# Prj_CamBienLua.net
KiCad netlist of a schematic drawn in Altium Designer
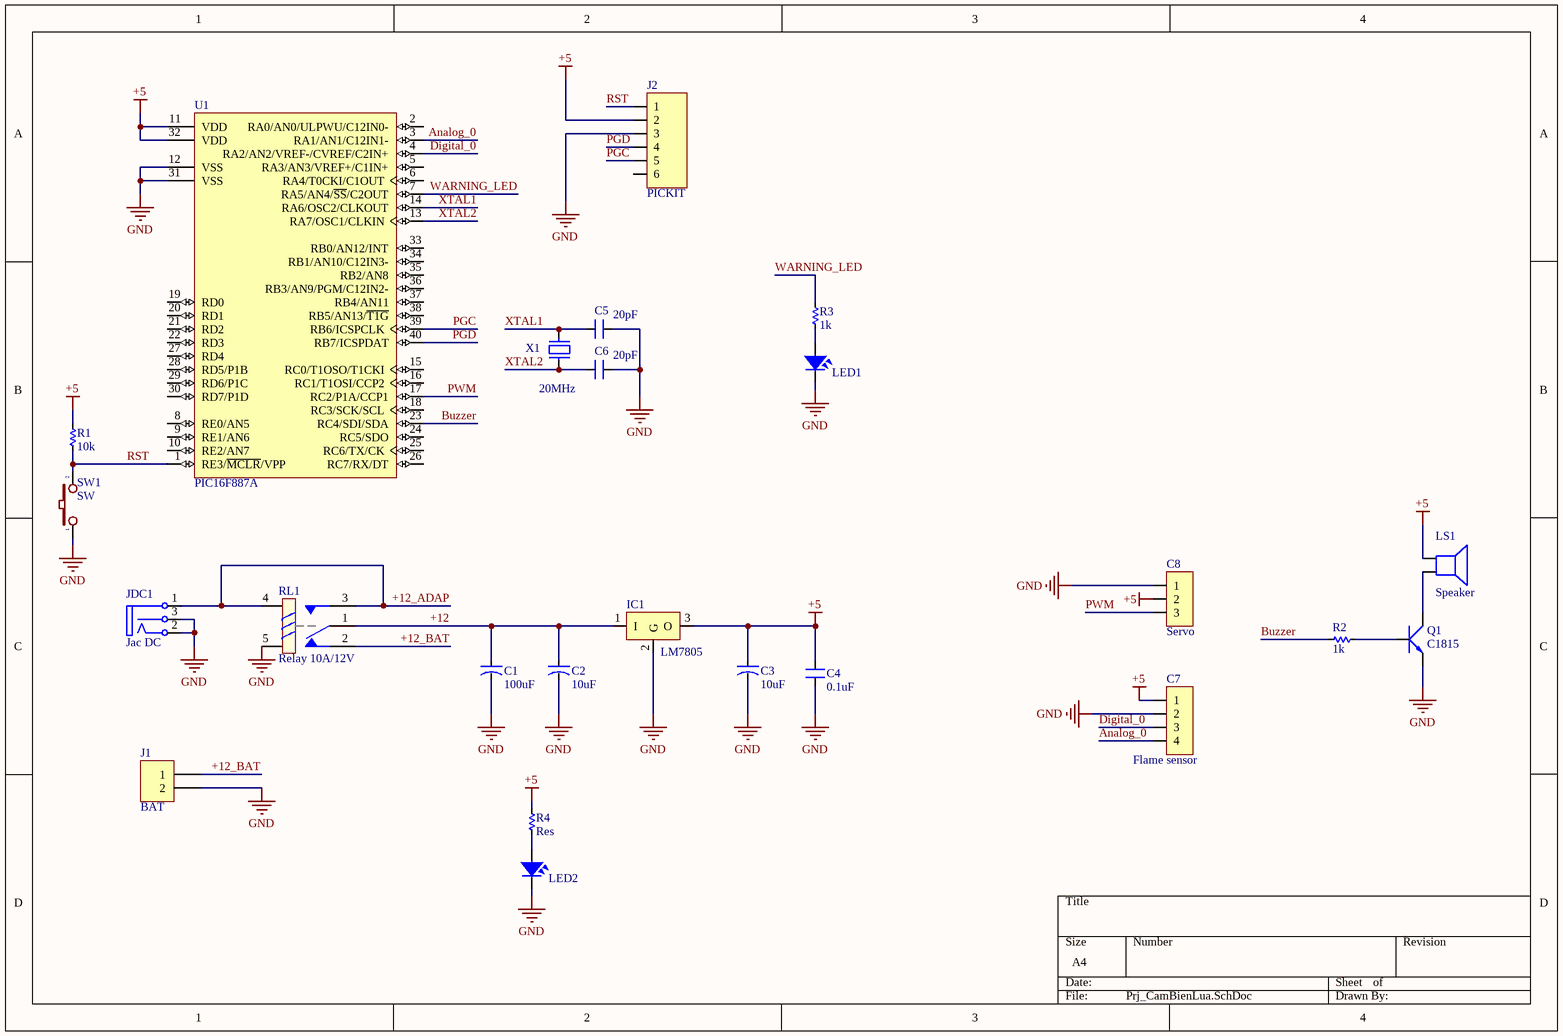
[diagram p0: Prj_CamBienLua.SchDoc]

(export (version "E")
  (design (tool "Eeschema 10.0.6"))
  (components
    (comp (ref "C1")
      (value "100uF")
      (footprint "CA-ALU-5")
      (description "Capacitor (Semiconductor SIM Model)")
      (fields (field (name "PUBLISHER") "Altium Limited"))
      (libsource (lib "Library") (part "CN-ALU-DIP"))
    )
    (comp (ref "C2")
      (value "10uF")
      (footprint "CA-ALU-5")
      (description "Capacitor (Semiconductor SIM Model)")
      (fields (field (name "PUBLISHER") "Altium Limited"))
      (libsource (lib "Library") (part "CN-ALU-DIP"))
    )
    (comp (ref "C3")
      (value "10uF")
      (footprint "CA-ALU-5")
      (description "Capacitor (Semiconductor SIM Model)")
      (fields (field (name "PUBLISHER") "Altium Limited"))
      (libsource (lib "Library") (part "CN-ALU-DIP"))
    )
    (comp (ref "C4") (value "0.1uF") (footprint "CN1.5") (libsource (lib "Library") (part "CN")))
    (comp (ref "C5") (value "20pF") (footprint "CN1.5") (libsource (lib "Library") (part "CN")))
    (comp (ref "C6") (value "20pF") (footprint "CN1.5") (libsource (lib "Library") (part "CN")))
    (comp (ref "C7")
      (value "Flame sensor")
      (footprint "JP4-C1T")
      (description "WR-PHD 2.54 mm Angled Socket Header")
      (fields
        (field (name "MANUFACTURER") "Würth Elektronik eiSos GmbH")
        (field (name "PARTNO") "613004143121")
        (field (name "CREATED BY") "Karrer Zheng")
      )
      (libsource (lib "Library") (part "JP4"))
    )
    (comp (ref "C8")
      (value "Servo")
      (footprint "JP3-D1T")
      (description "WR-PHD 2.54 mm Angled Socket Header")
      (fields
        (field (name "MANUFACTURER") "Würth Elektronik eiSos GmbH")
        (field (name "PARTNO") "613003143121")
        (field (name "CREATED BY") "Karrer Zheng")
      )
      (libsource (lib "Library") (part "JP3"))
    )
    (comp (ref "IC1")
      (value "LM7805")
      (footprint "TO220-123")
      (description "Positive Voltage Regulator")
      (fields (field (name "PUBLISHER") "Altium Limited"))
      (libsource (lib "Library") (part "LM78xx"))
    )
    (comp (ref "J1")
      (value "BAT")
      (footprint "KF2-5.08")
      (fields
        (field (name "MANUFACTURER") "Würth Elektronik eiSos GmbH")
        (field (name "PARTNO") "691103110002")
        (field (name "CREATED BY") "Karrer Zheng")
      )
      (libsource (lib "Library") (part "KF2"))
    )
    (comp (ref "J2")
      (value "PICKIT")
      (footprint "JP6-C1T")
      (description "WR-PHD 2.54 mm Angled Socket Header")
      (fields
        (field (name "MANUFACTURER") "Würth Elektronik eiSos GmbH")
        (field (name "PARTNO") "613006143121")
        (field (name "CREATED BY") "Karrer Zheng")
      )
      (libsource (lib "Library") (part "JP6"))
    )
    (comp (ref "JDC1")
      (value "Jac DC")
      (footprint "DC0")
      (description "Jac DC input")
      (libsource (lib "Library") (part "DCIN"))
    )
    (comp (ref "LED1")
      (value "LED")
      (footprint "LED-3MM-RED")
      (description "LED Single colour Green and Red")
      (libsource (lib "Library") (part "LED"))
    )
    (comp (ref "LED2")
      (value "LED")
      (footprint "LED-3MM-RED")
      (description "LED Single colour Green and Red")
      (libsource (lib "Library") (part "LED"))
    )
    (comp (ref "LS1")
      (value "Speaker")
      (footprint "SPEAKER")
      (description "Loudspeaker")
      (fields (field (name "PUBLISHER") "Altium Limited"))
      (libsource (lib "Library") (part "Speaker"))
    )
    (comp (ref "Q1")
      (value "C1815")
      (footprint "TO92-123")
      (description "NPN 600mW, ECB")
      (libsource (lib "Library") (part "C458"))
    )
    (comp (ref "R1")
      (value "10k")
      (footprint "RES-1/4W")
      (description "Res")
      (fields
        (field (name "MANUFACTURER") "Generic Components")
        (field (name "PUBLISHER") "Altium Hobart Technology Centre")
      )
      (libsource (lib "Library") (part "Res"))
    )
    (comp (ref "R2")
      (value "1k")
      (footprint "RES-1/4W")
      (description "Res")
      (fields
        (field (name "MANUFACTURER") "Generic Components")
        (field (name "PUBLISHER") "Altium Hobart Technology Centre")
      )
      (libsource (lib "Library") (part "Res"))
    )
    (comp (ref "R3")
      (value "1k")
      (footprint "RES-1/4W")
      (description "Res")
      (fields
        (field (name "MANUFACTURER") "Generic Components")
        (field (name "PUBLISHER") "Altium Hobart Technology Centre")
      )
      (libsource (lib "Library") (part "Res"))
    )
    (comp (ref "R4")
      (value "Res")
      (footprint "RES-1/4W")
      (fields
        (field (name "MANUFACTURER") "Generic Components")
        (field (name "PUBLISHER") "Altium Hobart Technology Centre")
      )
      (libsource (lib "Library") (part "Res"))
    )
    (comp (ref "RL1")
      (value "Relay 10A/12V")
      (footprint "Relay - SRD-03VDC-SL-C")
      (description "Relay SPDT,10A - 12VDC 5 Pin")
      (libsource (lib "Library") (part "Relay 5"))
    )
    (comp (ref "SW1")
      (value "SW")
      (footprint "SW2-DIP")
      (description "Switch button 2 pin")
      (libsource (lib "Library") (part "SW2"))
    )
    (comp (ref "U1")
      (value "PIC16F887A")
      (footprint "DIP40/W0.6")
      (fields (field (name "PUBLISHER") "Altium Limited"))
      (libsource (lib "Library") (part "PIC16F887-PU"))
    )
    (comp (ref "X1")
      (value "20MHz")
      (footprint "XT2")
      (description "Crystal, 32.768 KHz, -40 to 85 degC, 3.2 x 1.5 x 0.9 mm SMD")
      (libsource (lib "Library") (part "XT2"))
    )
  )
  (nets
    (net (code "1") (name "+5") (class "Default")
      (node (ref "C3") (pin "1") (pinfunction "1_1") (pintype "passive"))
      (node (ref "C4") (pin "2") (pinfunction "2_2") (pintype "passive"))
      (node (ref "C7") (pin "1") (pinfunction "1_1") (pintype "passive"))
      (node (ref "C8") (pin "2") (pinfunction "2_2") (pintype "passive"))
      (node (ref "IC1") (pin "3") (pinfunction "O_3") (pintype "power_in"))
      (node (ref "J2") (pin "2") (pinfunction "2_2") (pintype "passive"))
      (node (ref "LS1") (pin "1") (pinfunction "1_1") (pintype "passive"))
      (node (ref "R1") (pin "2") (pinfunction "2_2") (pintype "passive"))
      (node (ref "R4") (pin "1") (pinfunction "1_1") (pintype "passive"))
      (node (ref "U1") (pin "11") (pinfunction "VDD_11") (pintype "power_in"))
      (node (ref "U1") (pin "32") (pinfunction "VDD_32") (pintype "power_in"))
    )
    (net (code "2") (name "/+12") (class "Default")
      (node (ref "C1") (pin "1") (pinfunction "1_1") (pintype "passive"))
      (node (ref "C2") (pin "1") (pinfunction "1_1") (pintype "passive"))
      (node (ref "IC1") (pin "1") (pinfunction "I_1") (pintype "power_in"))
      (node (ref "RL1") (pin "1") (pinfunction "1_1") (pintype "passive"))
    )
    (net (code "3") (name "/+12_ADAP") (class "Default")
      (node (ref "JDC1") (pin "1") (pinfunction "T_1") (pintype "passive"))
      (node (ref "RL1") (pin "3") (pinfunction "3_3") (pintype "passive"))
      (node (ref "RL1") (pin "4") (pinfunction "4_4") (pintype "passive"))
    )
    (net (code "4") (name "/+12_BAT") (class "Default")
      (node (ref "J1") (pin "1") (pinfunction "1_1") (pintype "passive"))
      (node (ref "RL1") (pin "2") (pinfunction "2_2") (pintype "passive"))
    )
    (net (code "5") (name "/Analog_0") (class "Default")
      (node (ref "C7") (pin "4") (pinfunction "4_4") (pintype "passive"))
      (node (ref "U1") (pin "3") (pinfunction "RA1/AN1/C12IN1-_3") (pintype "bidirectional"))
    )
    (net (code "6") (name "/Buzzer") (class "Default")
      (node (ref "R2") (pin "1") (pinfunction "1_1") (pintype "passive"))
      (node (ref "U1") (pin "23") (pinfunction "RC4/SDI/SDA_23") (pintype "bidirectional"))
    )
    (net (code "7") (name "/Digital_0") (class "Default")
      (node (ref "C7") (pin "3") (pinfunction "3_3") (pintype "passive"))
      (node (ref "U1") (pin "4") (pinfunction "RA2/AN2/VREF-/CVREF/C2IN+_4") (pintype "bidirectional"))
    )
    (net (code "8") (name "/PGC") (class "Default")
      (node (ref "J2") (pin "5") (pinfunction "5_5") (pintype "passive"))
      (node (ref "U1") (pin "39") (pinfunction "RB6/ICSPCLK_39") (pintype "bidirectional"))
    )
    (net (code "9") (name "/PGD") (class "Default")
      (node (ref "J2") (pin "4") (pinfunction "4_4") (pintype "passive"))
      (node (ref "U1") (pin "40") (pinfunction "RB7/ICSPDAT_40") (pintype "bidirectional"))
    )
    (net (code "10") (name "/PWM") (class "Default")
      (node (ref "C8") (pin "3") (pinfunction "3_3") (pintype "passive"))
      (node (ref "U1") (pin "17") (pinfunction "RC2/P1A/CCP1_17") (pintype "bidirectional"))
    )
    (net (code "11") (name "/RST") (class "Default")
      (node (ref "J2") (pin "1") (pinfunction "1_1") (pintype "passive"))
      (node (ref "R1") (pin "1") (pinfunction "1_1") (pintype "passive"))
      (node (ref "SW1") (pin "2") (pinfunction "2_2") (pintype "passive"))
      (node (ref "U1") (pin "1") (pinfunction "RE3/~{MCLR}/VPP_1") (pintype "bidirectional"))
    )
    (net (code "12") (name "/WARNING_LED") (class "Default")
      (node (ref "R3") (pin "1") (pinfunction "1_1") (pintype "passive"))
      (node (ref "U1") (pin "7") (pinfunction "RA5/AN4/~{SS}/C2OUT_7") (pintype "bidirectional"))
    )
    (net (code "13") (name "/XTAL1") (class "Default")
      (node (ref "C5") (pin "1") (pinfunction "1_1") (pintype "passive"))
      (node (ref "U1") (pin "14") (pinfunction "RA6/OSC2/CLKOUT_14") (pintype "bidirectional"))
      (node (ref "X1") (pin "2") (pinfunction "2_2") (pintype "passive"))
    )
    (net (code "14") (name "/XTAL2") (class "Default")
      (node (ref "C6") (pin "1") (pinfunction "1_1") (pintype "passive"))
      (node (ref "U1") (pin "13") (pinfunction "RA7/OSC1/CLKIN_13") (pintype "bidirectional"))
      (node (ref "X1") (pin "1") (pinfunction "1_1") (pintype "passive"))
    )
    (net (code "15") (name "GND") (class "Default")
      (node (ref "C1") (pin "2") (pinfunction "2_2") (pintype "passive"))
      (node (ref "C2") (pin "2") (pinfunction "2_2") (pintype "passive"))
      (node (ref "C3") (pin "2") (pinfunction "2_2") (pintype "passive"))
      (node (ref "C4") (pin "1") (pinfunction "1_1") (pintype "passive"))
      (node (ref "C5") (pin "2") (pinfunction "2_2") (pintype "passive"))
      (node (ref "C6") (pin "2") (pinfunction "2_2") (pintype "passive"))
      (node (ref "C7") (pin "2") (pinfunction "2_2") (pintype "passive"))
      (node (ref "C8") (pin "1") (pinfunction "1_1") (pintype "passive"))
      (node (ref "IC1") (pin "2") (pinfunction "G_2") (pintype "power_in"))
      (node (ref "J1") (pin "2") (pinfunction "2_2") (pintype "passive"))
      (node (ref "J2") (pin "3") (pinfunction "3_3") (pintype "passive"))
      (node (ref "JDC1") (pin "2") (pinfunction "TN_2") (pintype "passive"))
      (node (ref "JDC1") (pin "3") (pinfunction "S_3") (pintype "power_in"))
      (node (ref "LED1") (pin "2") (pinfunction "2_2") (pintype "passive"))
      (node (ref "LED2") (pin "2") (pinfunction "2_2") (pintype "passive"))
      (node (ref "Q1") (pin "1") (pinfunction "E_1") (pintype "passive"))
      (node (ref "RL1") (pin "5") (pinfunction "5_5") (pintype "passive"))
      (node (ref "SW1") (pin "1") (pinfunction "1_1") (pintype "passive"))
      (node (ref "U1") (pin "12") (pinfunction "VSS_12") (pintype "power_in"))
      (node (ref "U1") (pin "31") (pinfunction "VSS_31") (pintype "power_in"))
    )
    (net (code "16") (name "Net-(LED1-Pad1)") (class "Default")
      (node (ref "LED1") (pin "1") (pinfunction "1_1") (pintype "passive"))
      (node (ref "R3") (pin "2") (pinfunction "2_2") (pintype "passive"))
    )
    (net (code "17") (name "Net-(LED2-Pad1)") (class "Default")
      (node (ref "LED2") (pin "1") (pinfunction "1_1") (pintype "passive"))
      (node (ref "R4") (pin "2") (pinfunction "2_2") (pintype "passive"))
    )
    (net (code "18") (name "Net-(Q1-B)") (class "Default")
      (node (ref "Q1") (pin "3") (pinfunction "B_3") (pintype "passive"))
      (node (ref "R2") (pin "2") (pinfunction "2_2") (pintype "passive"))
    )
    (net (code "19") (name "Net-(Q1-C)") (class "Default")
      (node (ref "LS1") (pin "2") (pinfunction "2_2") (pintype "passive"))
      (node (ref "Q1") (pin "2") (pinfunction "C_2") (pintype "passive"))
    )
    (net (code "20") (name "unconnected-(J2-Pad6)") (class "Default")
      (node (ref "J2") (pin "6") (pinfunction "6_6") (pintype "passive"))
    )
    (net (code "21") (name "unconnected-(U1-RA0{slash}AN0{slash}ULPWU{slash}C12IN0--Pad2)") (class "Default")
      (node (ref "U1") (pin "2") (pinfunction "RA0/AN0/ULPWU/C12IN0-_2") (pintype "bidirectional"))
    )
    (net (code "22") (name "unconnected-(U1-RA3{slash}AN3{slash}VREF+{slash}C1IN+-Pad5)") (class "Default")
      (node (ref "U1") (pin "5") (pinfunction "RA3/AN3/VREF+/C1IN+_5") (pintype "bidirectional"))
    )
    (net (code "23") (name "unconnected-(U1-RA4{slash}T0CKI{slash}C1OUT-Pad6)") (class "Default")
      (node (ref "U1") (pin "6") (pinfunction "RA4/T0CKI/C1OUT_6") (pintype "bidirectional"))
    )
    (net (code "24") (name "unconnected-(U1-RB0{slash}AN12{slash}INT-Pad33)") (class "Default")
      (node (ref "U1") (pin "33") (pinfunction "RB0/AN12/INT_33") (pintype "bidirectional"))
    )
    (net (code "25") (name "unconnected-(U1-RB1{slash}AN10{slash}C12IN3--Pad34)") (class "Default")
      (node (ref "U1") (pin "34") (pinfunction "RB1/AN10/C12IN3-_34") (pintype "bidirectional"))
    )
    (net (code "26") (name "unconnected-(U1-RB2{slash}AN8-Pad35)") (class "Default")
      (node (ref "U1") (pin "35") (pinfunction "RB2/AN8_35") (pintype "bidirectional"))
    )
    (net (code "27") (name "unconnected-(U1-RB3{slash}AN9{slash}PGM{slash}C12IN2--Pad36)") (class "Default")
      (node (ref "U1") (pin "36") (pinfunction "RB3/AN9/PGM/C12IN2-_36") (pintype "bidirectional"))
    )
    (net (code "28") (name "unconnected-(U1-RB4{slash}AN11-Pad37)") (class "Default")
      (node (ref "U1") (pin "37") (pinfunction "RB4/AN11_37") (pintype "bidirectional"))
    )
    (net (code "29") (name "unconnected-(U1-RB5{slash}AN13{slash}~{T1G}-Pad38)") (class "Default")
      (node (ref "U1") (pin "38") (pinfunction "RB5/AN13/~{T1G}_38") (pintype "bidirectional"))
    )
    (net (code "30") (name "unconnected-(U1-RC0{slash}T1OSO{slash}T1CKI-Pad15)") (class "Default")
      (node (ref "U1") (pin "15") (pinfunction "RC0/T1OSO/T1CKI_15") (pintype "bidirectional"))
    )
    (net (code "31") (name "unconnected-(U1-RC1{slash}T1OSI{slash}CCP2-Pad16)") (class "Default")
      (node (ref "U1") (pin "16") (pinfunction "RC1/T1OSI/CCP2_16") (pintype "bidirectional"))
    )
    (net (code "32") (name "unconnected-(U1-RC3{slash}SCK{slash}SCL-Pad18)") (class "Default")
      (node (ref "U1") (pin "18") (pinfunction "RC3/SCK/SCL_18") (pintype "bidirectional"))
    )
    (net (code "33") (name "unconnected-(U1-RC5{slash}SDO-Pad24)") (class "Default")
      (node (ref "U1") (pin "24") (pinfunction "RC5/SDO_24") (pintype "bidirectional"))
    )
    (net (code "34") (name "unconnected-(U1-RC6{slash}TX{slash}CK-Pad25)") (class "Default")
      (node (ref "U1") (pin "25") (pinfunction "RC6/TX/CK_25") (pintype "bidirectional"))
    )
    (net (code "35") (name "unconnected-(U1-RC7{slash}RX{slash}DT-Pad26)") (class "Default")
      (node (ref "U1") (pin "26") (pinfunction "RC7/RX/DT_26") (pintype "bidirectional"))
    )
    (net (code "36") (name "unconnected-(U1-RD0-Pad19)") (class "Default")
      (node (ref "U1") (pin "19") (pinfunction "RD0_19") (pintype "bidirectional"))
    )
    (net (code "37") (name "unconnected-(U1-RD1-Pad20)") (class "Default")
      (node (ref "U1") (pin "20") (pinfunction "RD1_20") (pintype "bidirectional"))
    )
    (net (code "38") (name "unconnected-(U1-RD2-Pad21)") (class "Default")
      (node (ref "U1") (pin "21") (pinfunction "RD2_21") (pintype "bidirectional"))
    )
    (net (code "39") (name "unconnected-(U1-RD3-Pad22)") (class "Default")
      (node (ref "U1") (pin "22") (pinfunction "RD3_22") (pintype "bidirectional"))
    )
    (net (code "40") (name "unconnected-(U1-RD4-Pad27)") (class "Default")
      (node (ref "U1") (pin "27") (pinfunction "RD4_27") (pintype "bidirectional"))
    )
    (net (code "41") (name "unconnected-(U1-RD5{slash}P1B-Pad28)") (class "Default")
      (node (ref "U1") (pin "28") (pinfunction "RD5/P1B_28") (pintype "bidirectional"))
    )
    (net (code "42") (name "unconnected-(U1-RD6{slash}P1C-Pad29)") (class "Default")
      (node (ref "U1") (pin "29") (pinfunction "RD6/P1C_29") (pintype "bidirectional"))
    )
    (net (code "43") (name "unconnected-(U1-RD7{slash}P1D-Pad30)") (class "Default")
      (node (ref "U1") (pin "30") (pinfunction "RD7/P1D_30") (pintype "bidirectional"))
    )
    (net (code "44") (name "unconnected-(U1-RE0{slash}AN5-Pad8)") (class "Default")
      (node (ref "U1") (pin "8") (pinfunction "RE0/AN5_8") (pintype "bidirectional"))
    )
    (net (code "45") (name "unconnected-(U1-RE1{slash}AN6-Pad9)") (class "Default")
      (node (ref "U1") (pin "9") (pinfunction "RE1/AN6_9") (pintype "bidirectional"))
    )
    (net (code "46") (name "unconnected-(U1-RE2{slash}AN7-Pad10)") (class "Default")
      (node (ref "U1") (pin "10") (pinfunction "RE2/AN7_10") (pintype "bidirectional"))
    )
  )
)
